# zTable.net
KiCad netlist of a schematic drawn in EAGLE
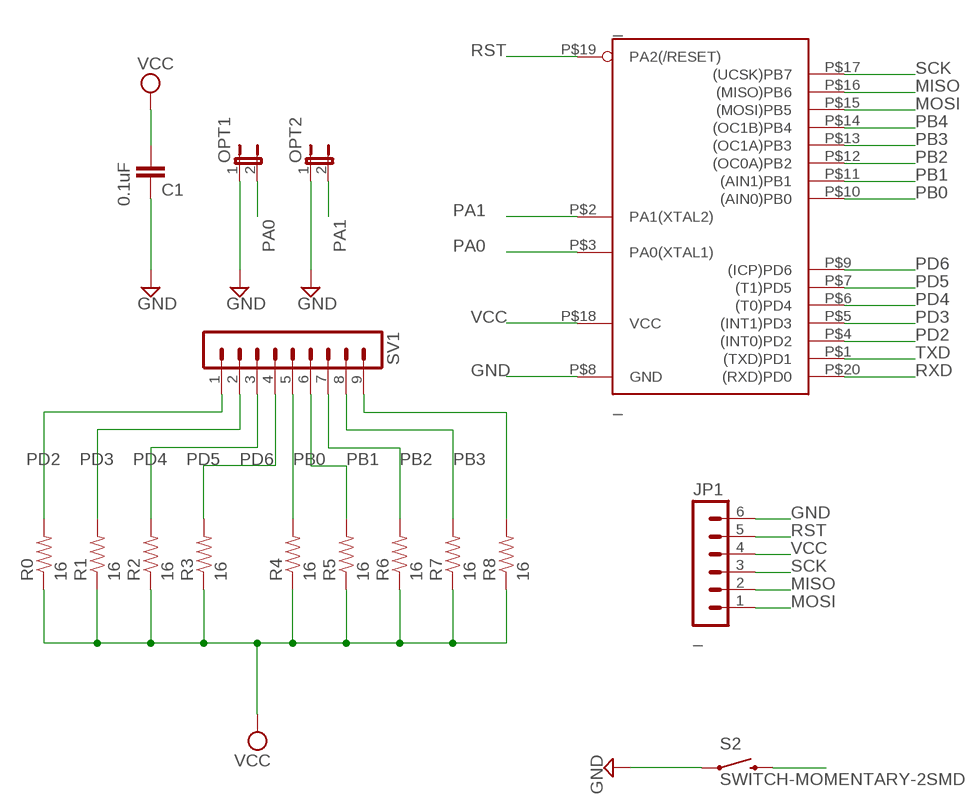
[diagram p0: schematic, sheet 1]

(export (version "E")
  (design (tool "Eeschema 10.0.6"))
  (components
    (comp (ref "C1")
      (value "0.1uF")
      (footprint "eagle-import:0805")
      (libsource (lib "eagle-import") (part "CAP0805"))
    )
    (comp (ref "JP1")
      (value "_")
      (footprint "eagle-import:MA06-1")
      (libsource (lib "eagle-import") (part "MA06-1"))
    )
    (comp (ref "OPT1")
      (value "JUMPER-2PTH")
      (footprint "eagle-import:1X02")
      (libsource (lib "eagle-import") (part "JUMPER-2PTH"))
    )
    (comp (ref "OPT2")
      (value "JUMPER-2PTH")
      (footprint "eagle-import:1X02")
      (libsource (lib "eagle-import") (part "JUMPER-2PTH"))
    )
    (comp (ref "R0")
      (value "16")
      (footprint "eagle-import:0805")
      (libsource (lib "eagle-import") (part "RESISTOR"))
    )
    (comp (ref "R1")
      (value "16")
      (footprint "eagle-import:0805")
      (libsource (lib "eagle-import") (part "RESISTOR"))
    )
    (comp (ref "R2")
      (value "16")
      (footprint "eagle-import:0805")
      (libsource (lib "eagle-import") (part "RESISTOR"))
    )
    (comp (ref "R3")
      (value "16")
      (footprint "eagle-import:0805")
      (libsource (lib "eagle-import") (part "RESISTOR"))
    )
    (comp (ref "R4")
      (value "16")
      (footprint "eagle-import:0805")
      (libsource (lib "eagle-import") (part "RESISTOR"))
    )
    (comp (ref "R5")
      (value "16")
      (footprint "eagle-import:0805")
      (libsource (lib "eagle-import") (part "RESISTOR"))
    )
    (comp (ref "R6")
      (value "16")
      (footprint "eagle-import:0805")
      (libsource (lib "eagle-import") (part "RESISTOR"))
    )
    (comp (ref "R7")
      (value "16")
      (footprint "eagle-import:0805")
      (libsource (lib "eagle-import") (part "RESISTOR"))
    )
    (comp (ref "R8")
      (value "16")
      (footprint "eagle-import:0805")
      (libsource (lib "eagle-import") (part "RESISTOR"))
    )
    (comp (ref "S2")
      (value "SWITCH-MOMENTARY-2SMD")
      (footprint "eagle-import:TACTILE_SWITCH_SMD")
      (libsource (lib "eagle-import") (part "SWITCH-MOMENTARY-2SMD"))
    )
    (comp (ref "SV1")
      (value "MA09-1")
      (footprint "eagle-import:MA09-1")
      (libsource (lib "eagle-import") (part "MA09-1"))
    )
    (comp (ref "_")
      (value "_")
      (footprint "eagle-import:MLF20")
      (libsource (lib "eagle-import") (part "TINY2313-M"))
    )
  )
  (nets
    (net (code "1") (name "/MISO") (class "Default")
      (node (ref "JP1") (pin "2") (pinfunction "2_2") (pintype "passive"))
      (node (ref "_") (pin "P$16") (pinfunction "(MISO)PB6_P$16") (pintype "bidirectional"))
    )
    (net (code "2") (name "/MOSI") (class "Default")
      (node (ref "JP1") (pin "1") (pinfunction "1_1") (pintype "passive"))
      (node (ref "_") (pin "P$15") (pinfunction "(MOSI)PB5_P$15") (pintype "bidirectional"))
    )
    (net (code "3") (name "/PA0") (class "Default")
      (node (ref "OPT1") (pin "2") (pinfunction "2_2") (pintype "passive"))
      (node (ref "_") (pin "P$3") (pinfunction "PA0(XTAL1)_P$3") (pintype "bidirectional"))
    )
    (net (code "4") (name "/PA1") (class "Default")
      (node (ref "OPT2") (pin "2") (pinfunction "2_2") (pintype "passive"))
      (node (ref "_") (pin "P$2") (pinfunction "PA1(XTAL2)_P$2") (pintype "bidirectional"))
    )
    (net (code "5") (name "/PB0") (class "Default")
      (node (ref "R5") (pin "2") (pinfunction "2_2") (pintype "passive"))
      (node (ref "SV1") (pin "6") (pinfunction "6_6") (pintype "passive"))
      (node (ref "_") (pin "P$10") (pinfunction "(AIN0)PB0_P$10") (pintype "bidirectional"))
    )
    (net (code "6") (name "/PB1") (class "Default")
      (node (ref "R6") (pin "2") (pinfunction "2_2") (pintype "passive"))
      (node (ref "SV1") (pin "7") (pinfunction "7_7") (pintype "passive"))
      (node (ref "_") (pin "P$11") (pinfunction "(AIN1)PB1_P$11") (pintype "bidirectional"))
    )
    (net (code "7") (name "/PB2") (class "Default")
      (node (ref "R7") (pin "2") (pinfunction "2_2") (pintype "passive"))
      (node (ref "SV1") (pin "8") (pinfunction "8_8") (pintype "passive"))
      (node (ref "_") (pin "P$12") (pinfunction "(OC0A)PB2_P$12") (pintype "bidirectional"))
    )
    (net (code "8") (name "/PB3") (class "Default")
      (node (ref "R8") (pin "2") (pinfunction "2_2") (pintype "passive"))
      (node (ref "SV1") (pin "9") (pinfunction "9_9") (pintype "passive"))
      (node (ref "_") (pin "P$13") (pinfunction "(OC1A)PB3_P$13") (pintype "bidirectional"))
    )
    (net (code "9") (name "/PB4") (class "Default")
      (node (ref "S2") (pin "3") (pinfunction "2_3") (pintype "passive"))
      (node (ref "_") (pin "P$14") (pinfunction "(OC1B)PB4_P$14") (pintype "bidirectional"))
    )
    (net (code "10") (name "/PD2") (class "Default")
      (node (ref "R0") (pin "2") (pinfunction "2_2") (pintype "passive"))
      (node (ref "SV1") (pin "1") (pinfunction "1_1") (pintype "passive"))
      (node (ref "_") (pin "P$4") (pinfunction "(INT0)PD2_P$4") (pintype "bidirectional"))
    )
    (net (code "11") (name "/PD3") (class "Default")
      (node (ref "R1") (pin "2") (pinfunction "2_2") (pintype "passive"))
      (node (ref "SV1") (pin "2") (pinfunction "2_2") (pintype "passive"))
      (node (ref "_") (pin "P$5") (pinfunction "(INT1)PD3_P$5") (pintype "bidirectional"))
    )
    (net (code "12") (name "/PD4") (class "Default")
      (node (ref "R2") (pin "2") (pinfunction "2_2") (pintype "passive"))
      (node (ref "SV1") (pin "3") (pinfunction "3_3") (pintype "passive"))
      (node (ref "_") (pin "P$6") (pinfunction "(T0)PD4_P$6") (pintype "bidirectional"))
    )
    (net (code "13") (name "/PD5") (class "Default")
      (node (ref "R3") (pin "2") (pinfunction "2_2") (pintype "passive"))
      (node (ref "SV1") (pin "4") (pinfunction "4_4") (pintype "passive"))
      (node (ref "_") (pin "P$7") (pinfunction "(T1)PD5_P$7") (pintype "bidirectional"))
    )
    (net (code "14") (name "/PD6") (class "Default")
      (node (ref "R4") (pin "2") (pinfunction "2_2") (pintype "passive"))
      (node (ref "SV1") (pin "5") (pinfunction "5_5") (pintype "passive"))
      (node (ref "_") (pin "P$9") (pinfunction "(ICP)PD6_P$9") (pintype "bidirectional"))
    )
    (net (code "15") (name "/RST") (class "Default")
      (node (ref "JP1") (pin "5") (pinfunction "5_5") (pintype "passive"))
      (node (ref "_") (pin "P$19") (pinfunction "PA2(/RESET)_P$19") (pintype "input"))
    )
    (net (code "16") (name "/RXD") (class "Default")
      (node (ref "_") (pin "P$20") (pinfunction "(RXD)PD0_P$20") (pintype "bidirectional"))
    )
    (net (code "17") (name "/SCK") (class "Default")
      (node (ref "JP1") (pin "3") (pinfunction "3_3") (pintype "passive"))
      (node (ref "_") (pin "P$17") (pinfunction "(UCSK)PB7_P$17") (pintype "bidirectional"))
    )
    (net (code "18") (name "/TXD") (class "Default")
      (node (ref "_") (pin "P$1") (pinfunction "(TXD)PD1_P$1") (pintype "bidirectional"))
    )
    (net (code "19") (name "GND") (class "Default")
      (node (ref "C1") (pin "2") (pinfunction "2_2") (pintype "passive"))
      (node (ref "JP1") (pin "6") (pinfunction "6_6") (pintype "passive"))
      (node (ref "OPT1") (pin "1") (pinfunction "1_1") (pintype "passive"))
      (node (ref "OPT2") (pin "1") (pinfunction "1_1") (pintype "passive"))
      (node (ref "S2") (pin "1") (pinfunction "1_1") (pintype "passive"))
      (node (ref "_") (pin "P$8") (pinfunction "GND_P$8") (pintype "power_in"))
    )
    (net (code "20") (name "VCC") (class "Default")
      (node (ref "C1") (pin "1") (pinfunction "1_1") (pintype "passive"))
      (node (ref "JP1") (pin "4") (pinfunction "4_4") (pintype "passive"))
      (node (ref "R0") (pin "1") (pinfunction "1_1") (pintype "passive"))
      (node (ref "R1") (pin "1") (pinfunction "1_1") (pintype "passive"))
      (node (ref "R2") (pin "1") (pinfunction "1_1") (pintype "passive"))
      (node (ref "R3") (pin "1") (pinfunction "1_1") (pintype "passive"))
      (node (ref "R4") (pin "1") (pinfunction "1_1") (pintype "passive"))
      (node (ref "R5") (pin "1") (pinfunction "1_1") (pintype "passive"))
      (node (ref "R6") (pin "1") (pinfunction "1_1") (pintype "passive"))
      (node (ref "R7") (pin "1") (pinfunction "1_1") (pintype "passive"))
      (node (ref "R8") (pin "1") (pinfunction "1_1") (pintype "passive"))
      (node (ref "_") (pin "P$18") (pinfunction "VCC_P$18") (pintype "power_in"))
    )
  )
)
